# tohuart.net
KiCad netlist of a schematic drawn in EAGLE
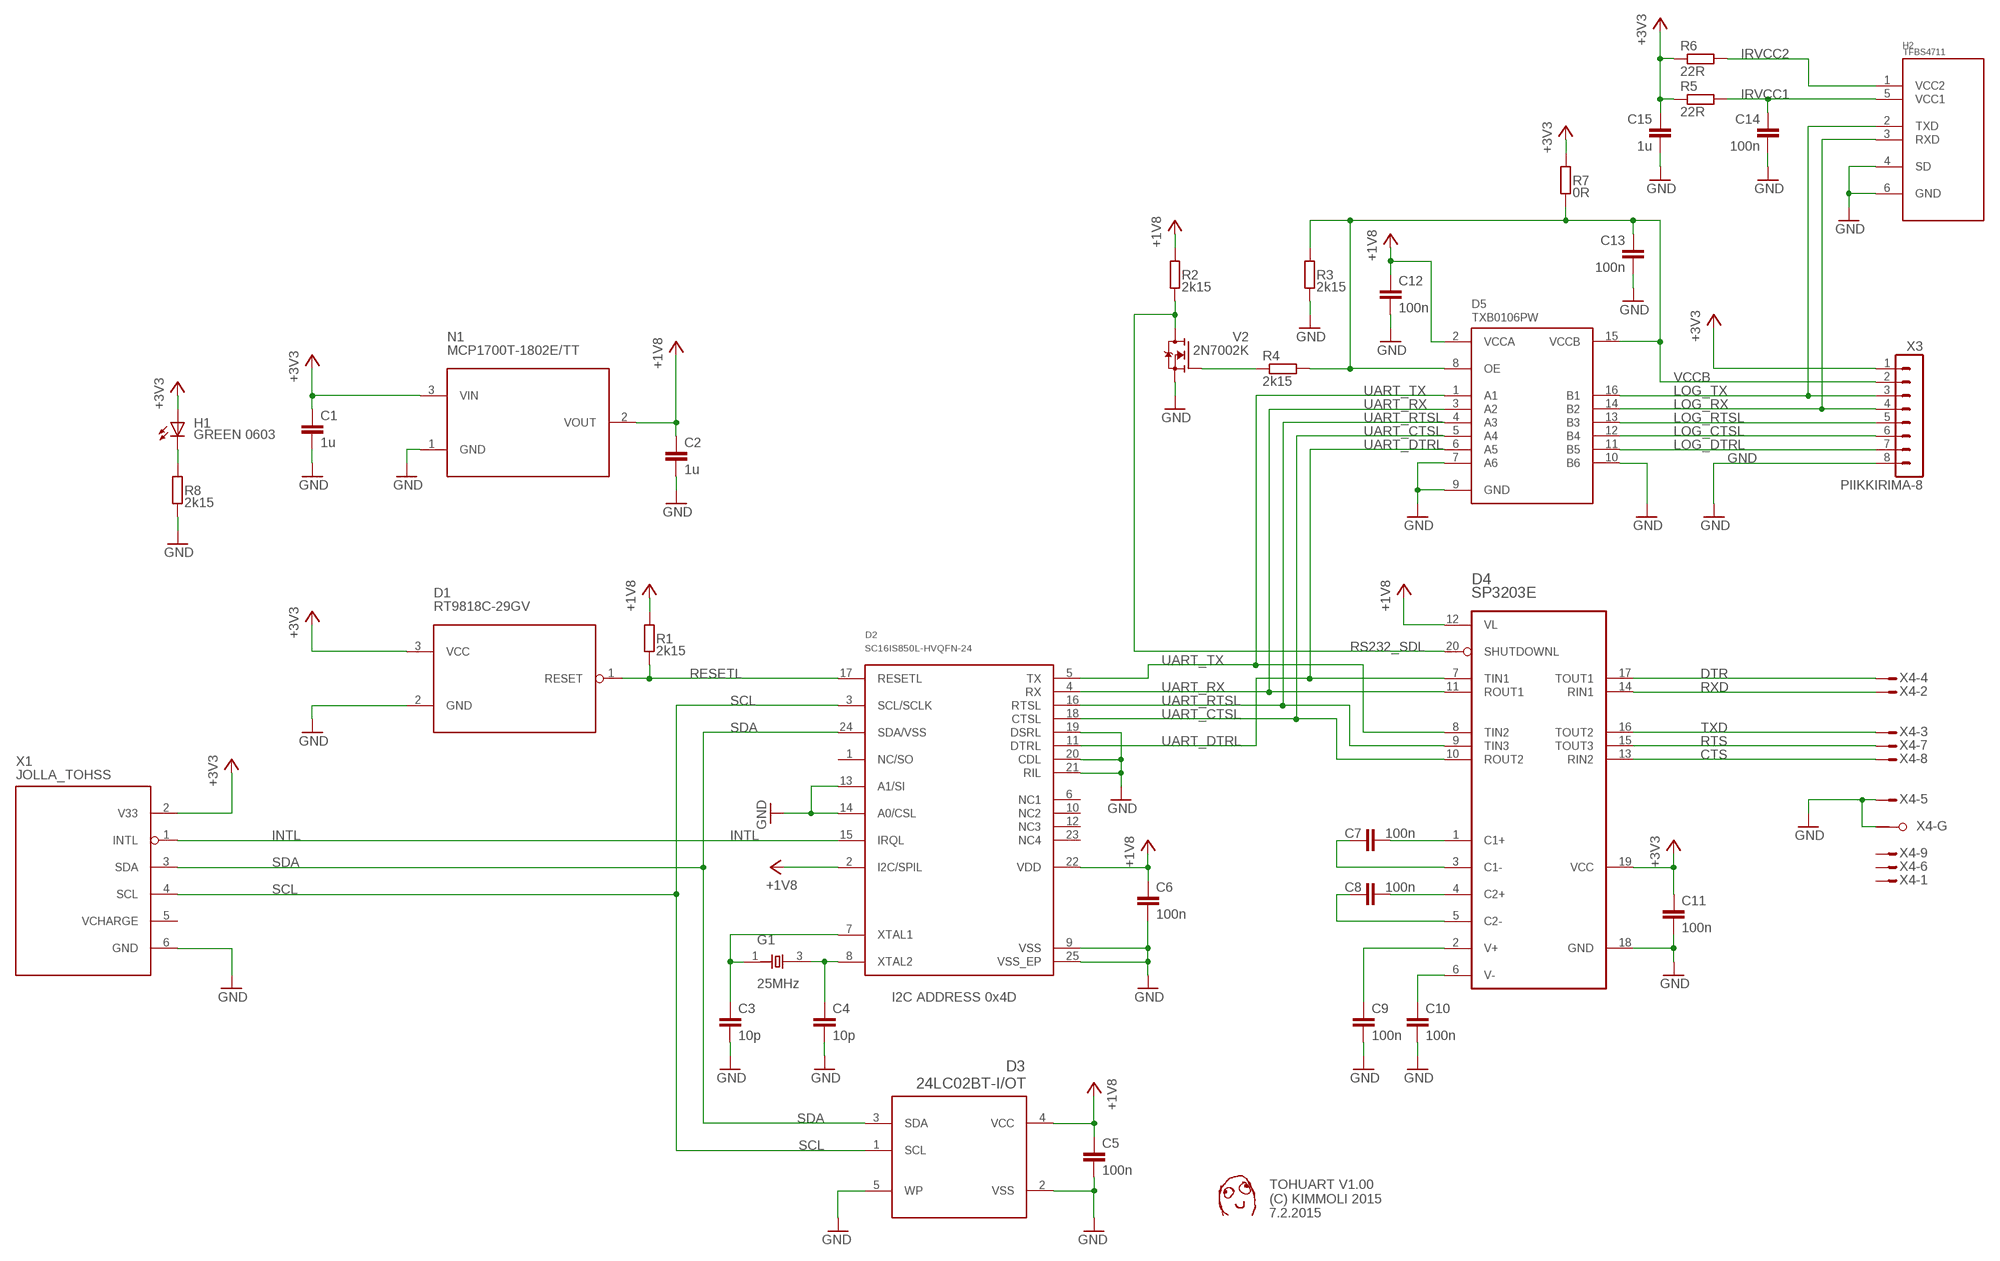
[diagram p0: schematic, sheet 1]

(export (version "E")
  (design (tool "Eeschema 10.0.6"))
  (components
    (comp (ref "C1")
      (value "1u")
      (footprint "eagle-import:C0603")
      (libsource (lib "eagle-import") (part "C-EUC0603"))
    )
    (comp (ref "C2")
      (value "1u")
      (footprint "eagle-import:C0603")
      (libsource (lib "eagle-import") (part "C-EUC0603"))
    )
    (comp (ref "C3")
      (value "10p")
      (footprint "eagle-import:C0603")
      (libsource (lib "eagle-import") (part "C-EUC0603"))
    )
    (comp (ref "C4")
      (value "10p")
      (footprint "eagle-import:C0603")
      (libsource (lib "eagle-import") (part "C-EUC0603"))
    )
    (comp (ref "C5")
      (value "100n")
      (footprint "eagle-import:C0603")
      (libsource (lib "eagle-import") (part "C-EUC0603"))
    )
    (comp (ref "C6")
      (value "100n")
      (footprint "eagle-import:C0603")
      (libsource (lib "eagle-import") (part "C-EUC0603"))
    )
    (comp (ref "C7")
      (value "100n")
      (footprint "eagle-import:C0603")
      (libsource (lib "eagle-import") (part "C-EUC0603"))
    )
    (comp (ref "C8")
      (value "100n")
      (footprint "eagle-import:C0603")
      (libsource (lib "eagle-import") (part "C-EUC0603"))
    )
    (comp (ref "C9")
      (value "100n")
      (footprint "eagle-import:C0603")
      (libsource (lib "eagle-import") (part "C-EUC0603"))
    )
    (comp (ref "C10")
      (value "100n")
      (footprint "eagle-import:C0603")
      (libsource (lib "eagle-import") (part "C-EUC0603"))
    )
    (comp (ref "C11")
      (value "100n")
      (footprint "eagle-import:C0603")
      (libsource (lib "eagle-import") (part "C-EUC0603"))
    )
    (comp (ref "C12")
      (value "100n")
      (footprint "eagle-import:C0603")
      (libsource (lib "eagle-import") (part "C-EUC0603"))
    )
    (comp (ref "C13")
      (value "100n")
      (footprint "eagle-import:C0603")
      (libsource (lib "eagle-import") (part "C-EUC0603"))
    )
    (comp (ref "C14")
      (value "100n")
      (footprint "eagle-import:C0603")
      (libsource (lib "eagle-import") (part "C-EUC0603"))
    )
    (comp (ref "C15")
      (value "1u")
      (footprint "eagle-import:C0603")
      (libsource (lib "eagle-import") (part "C-EUC0603"))
    )
    (comp (ref "D1")
      (value "RT9818C-29GV")
      (footprint "eagle-import:SOT23")
      (libsource (lib "eagle-import") (part "RT9818C-29GV"))
    )
    (comp (ref "D2")
      (value "SC16IS850L-HVQFN-24")
      (footprint "eagle-import:HVQFN-24")
      (libsource (lib "eagle-import") (part "SC16IS850L-HVQFN-24"))
    )
    (comp (ref "D3")
      (value "24LC02BT-I/OT")
      (footprint "eagle-import:SOT95P280X145-5N")
      (libsource (lib "eagle-import") (part "24LC02BT-I/OT"))
    )
    (comp (ref "D4")
      (value "SP3203E")
      (footprint "eagle-import:TSSOP-20")
      (libsource (lib "eagle-import") (part "SP3203E"))
    )
    (comp (ref "D5")
      (value "TXB0106PW")
      (footprint "eagle-import:TSSOP-16-065")
      (libsource (lib "eagle-import") (part "TXB0106PW"))
    )
    (comp (ref "G1")
      (value "25MHz")
      (footprint "eagle-import:X_3225")
      (libsource (lib "eagle-import") (part "XTAL_3225_SMD"))
    )
    (comp (ref "H1")
      (value "GREEN 0603")
      (footprint "eagle-import:CHIP-LED0603")
      (libsource (lib "eagle-import") (part "LEDCHIP-LED0603"))
    )
    (comp (ref "H2")
      (value "TFBS4711")
      (footprint "eagle-import:TFBS4711")
      (libsource (lib "eagle-import") (part "TFBS4711"))
    )
    (comp (ref "N1")
      (value "MCP1700T-1802E/TT")
      (footprint "eagle-import:SOT23")
      (libsource (lib "eagle-import") (part "MCP1700T-1802E/TT"))
    )
    (comp (ref "R1")
      (value "2k15")
      (footprint "eagle-import:R0603")
      (libsource (lib "eagle-import") (part "R-EU_R0603"))
    )
    (comp (ref "R2")
      (value "2k15")
      (footprint "eagle-import:R0603")
      (libsource (lib "eagle-import") (part "R-EU_R0603"))
    )
    (comp (ref "R3")
      (value "2k15")
      (footprint "eagle-import:R0603")
      (libsource (lib "eagle-import") (part "R-EU_R0603"))
    )
    (comp (ref "R4")
      (value "2k15")
      (footprint "eagle-import:R0603")
      (libsource (lib "eagle-import") (part "R-EU_R0603"))
    )
    (comp (ref "R5")
      (value "22R")
      (footprint "eagle-import:R0603")
      (libsource (lib "eagle-import") (part "R-EU_R0603"))
    )
    (comp (ref "R6")
      (value "22R")
      (footprint "eagle-import:R0603")
      (libsource (lib "eagle-import") (part "R-EU_R0603"))
    )
    (comp (ref "R7")
      (value "0R")
      (footprint "eagle-import:R0603")
      (libsource (lib "eagle-import") (part "R-EU_R0603"))
    )
    (comp (ref "R8")
      (value "2k15")
      (footprint "eagle-import:R0603")
      (libsource (lib "eagle-import") (part "R-EU_R0603"))
    )
    (comp (ref "U$1")
      (value "DAFUG")
      (footprint "eagle-import:DAFUG")
      (libsource (lib "eagle-import") (part "DAFUG"))
    )
    (comp (ref "V2")
      (value "2N7002K")
      (footprint "eagle-import:SOT23")
      (libsource (lib "eagle-import") (part "2N7002K"))
    )
    (comp (ref "X1")
      (value "JOLLA_TOHSS")
      (footprint "eagle-import:JOLLA_TOH_POGOPADS")
      (libsource (lib "eagle-import") (part "JOLLA_TOHSS"))
    )
    (comp (ref "X3")
      (value "PIIKKIRIMA-8")
      (footprint "eagle-import:PIIKKIRIMA-8")
      (libsource (lib "eagle-import") (part "PIIKKIRIMA-8"))
    )
    (comp (ref "X4")
      (value "M09VPS")
      (footprint "eagle-import:M09VP")
      (libsource (lib "eagle-import") (part "M09VPS"))
    )
  )
  (nets
    (net (code "1") (name "+1V8") (class "Default")
      (node (ref "C12") (pin "1") (pinfunction "1_1") (pintype "passive"))
      (node (ref "C2") (pin "1") (pinfunction "1_1") (pintype "passive"))
      (node (ref "C5") (pin "1") (pinfunction "1_1") (pintype "passive"))
      (node (ref "C6") (pin "1") (pinfunction "1_1") (pintype "passive"))
      (node (ref "D2") (pin "2") (pinfunction "I2C/SPIL_2") (pintype "bidirectional"))
      (node (ref "D2") (pin "22") (pinfunction "VDD_22") (pintype "bidirectional"))
      (node (ref "D3") (pin "4") (pinfunction "VCC_4") (pintype "power_in"))
      (node (ref "D4") (pin "12") (pinfunction "VL_12") (pintype "passive"))
      (node (ref "D5") (pin "2") (pinfunction "VCCA_2") (pintype "bidirectional"))
      (node (ref "N1") (pin "2") (pinfunction "VOUT_2") (pintype "bidirectional"))
      (node (ref "R1") (pin "2") (pinfunction "2_2") (pintype "passive"))
      (node (ref "R2") (pin "2") (pinfunction "2_2") (pintype "passive"))
    )
    (net (code "2") (name "+3V3") (class "Default")
      (node (ref "C1") (pin "1") (pinfunction "1_1") (pintype "passive"))
      (node (ref "C11") (pin "1") (pinfunction "1_1") (pintype "passive"))
      (node (ref "C15") (pin "1") (pinfunction "1_1") (pintype "passive"))
      (node (ref "D1") (pin "3") (pinfunction "VCC_3") (pintype "bidirectional"))
      (node (ref "D4") (pin "19") (pinfunction "VCC_19") (pintype "power_in"))
      (node (ref "H1") (pin "A") (pinfunction "A_A") (pintype "passive"))
      (node (ref "N1") (pin "3") (pinfunction "VIN_3") (pintype "bidirectional"))
      (node (ref "R5") (pin "1") (pinfunction "1_1") (pintype "passive"))
      (node (ref "R6") (pin "1") (pinfunction "1_1") (pintype "passive"))
      (node (ref "R7") (pin "2") (pinfunction "2_2") (pintype "passive"))
      (node (ref "X1") (pin "2") (pinfunction "V33_2") (pintype "bidirectional"))
      (node (ref "X3") (pin "1") (pinfunction "1_1") (pintype "passive"))
    )
    (net (code "3") (name "/CTS") (class "Default")
      (node (ref "D4") (pin "13") (pinfunction "RIN2_13") (pintype "input"))
      (node (ref "X4") (pin "8") (pinfunction "M_8") (pintype "passive"))
    )
    (net (code "4") (name "/DTR") (class "Default")
      (node (ref "D4") (pin "17") (pinfunction "TOUT1_17") (pintype "output"))
      (node (ref "X4") (pin "4") (pinfunction "M_4") (pintype "passive"))
    )
    (net (code "5") (name "/INTL") (class "Default")
      (node (ref "D2") (pin "15") (pinfunction "IRQL_15") (pintype "bidirectional"))
      (node (ref "X1") (pin "1") (pinfunction "INTL_1") (pintype "bidirectional"))
    )
    (net (code "6") (name "/IRVCC1") (class "Default")
      (node (ref "C14") (pin "1") (pinfunction "1_1") (pintype "passive"))
      (node (ref "H2") (pin "5") (pinfunction "VCC1_5") (pintype "bidirectional"))
      (node (ref "R5") (pin "2") (pinfunction "2_2") (pintype "passive"))
    )
    (net (code "7") (name "/IRVCC2") (class "Default")
      (node (ref "H2") (pin "1") (pinfunction "VCC2_1") (pintype "bidirectional"))
      (node (ref "R6") (pin "2") (pinfunction "2_2") (pintype "passive"))
    )
    (net (code "8") (name "/LOG_CTSL") (class "Default")
      (node (ref "D5") (pin "12") (pinfunction "B4_12") (pintype "bidirectional"))
      (node (ref "X3") (pin "6") (pinfunction "6_6") (pintype "passive"))
    )
    (net (code "9") (name "/LOG_DTRL") (class "Default")
      (node (ref "D5") (pin "11") (pinfunction "B5_11") (pintype "bidirectional"))
      (node (ref "X3") (pin "7") (pinfunction "7_7") (pintype "passive"))
    )
    (net (code "10") (name "/LOG_RTSL") (class "Default")
      (node (ref "D5") (pin "13") (pinfunction "B3_13") (pintype "bidirectional"))
      (node (ref "X3") (pin "5") (pinfunction "5_5") (pintype "passive"))
    )
    (net (code "11") (name "/LOG_RX") (class "Default")
      (node (ref "D5") (pin "14") (pinfunction "B2_14") (pintype "bidirectional"))
      (node (ref "H2") (pin "3") (pinfunction "RXD_3") (pintype "bidirectional"))
      (node (ref "X3") (pin "4") (pinfunction "4_4") (pintype "passive"))
    )
    (net (code "12") (name "/LOG_TX") (class "Default")
      (node (ref "D5") (pin "16") (pinfunction "B1_16") (pintype "bidirectional"))
      (node (ref "H2") (pin "2") (pinfunction "TXD_2") (pintype "bidirectional"))
      (node (ref "X3") (pin "3") (pinfunction "3_3") (pintype "passive"))
    )
    (net (code "13") (name "/RESETL") (class "Default")
      (node (ref "D1") (pin "1") (pinfunction "RESET_1") (pintype "bidirectional"))
      (node (ref "D2") (pin "17") (pinfunction "RESETL_17") (pintype "bidirectional"))
      (node (ref "R1") (pin "1") (pinfunction "1_1") (pintype "passive"))
    )
    (net (code "14") (name "/RS232_SDL") (class "Default")
      (node (ref "D4") (pin "20") (pinfunction "SHUTDOWNL_20") (pintype "bidirectional"))
      (node (ref "R2") (pin "1") (pinfunction "1_1") (pintype "passive"))
      (node (ref "V2") (pin "3") (pinfunction "D_3") (pintype "passive"))
    )
    (net (code "15") (name "/RTS") (class "Default")
      (node (ref "D4") (pin "15") (pinfunction "TOUT3_15") (pintype "output"))
      (node (ref "X4") (pin "7") (pinfunction "M_7") (pintype "passive"))
    )
    (net (code "16") (name "/RXD") (class "Default")
      (node (ref "D4") (pin "14") (pinfunction "RIN1_14") (pintype "input"))
      (node (ref "X4") (pin "2") (pinfunction "M_2") (pintype "passive"))
    )
    (net (code "17") (name "/SCL") (class "Default")
      (node (ref "D2") (pin "3") (pinfunction "SCL/SCLK_3") (pintype "bidirectional"))
      (node (ref "D3") (pin "1") (pinfunction "SCL_1") (pintype "input"))
      (node (ref "X1") (pin "4") (pinfunction "SCL_4") (pintype "bidirectional"))
    )
    (net (code "18") (name "/SDA") (class "Default")
      (node (ref "D2") (pin "24") (pinfunction "SDA/VSS_24") (pintype "bidirectional"))
      (node (ref "D3") (pin "3") (pinfunction "SDA_3") (pintype "bidirectional"))
      (node (ref "X1") (pin "3") (pinfunction "SDA_3") (pintype "bidirectional"))
    )
    (net (code "19") (name "/TXD") (class "Default")
      (node (ref "D4") (pin "16") (pinfunction "TOUT2_16") (pintype "output"))
      (node (ref "X4") (pin "3") (pinfunction "M_3") (pintype "passive"))
    )
    (net (code "20") (name "/UART_CTSL") (class "Default")
      (node (ref "D2") (pin "18") (pinfunction "CTSL_18") (pintype "bidirectional"))
      (node (ref "D4") (pin "10") (pinfunction "ROUT2_10") (pintype "output"))
      (node (ref "D5") (pin "5") (pinfunction "A4_5") (pintype "bidirectional"))
    )
    (net (code "21") (name "/UART_DTRL") (class "Default")
      (node (ref "D2") (pin "11") (pinfunction "DTRL_11") (pintype "bidirectional"))
      (node (ref "D4") (pin "7") (pinfunction "TIN1_7") (pintype "input"))
      (node (ref "D5") (pin "6") (pinfunction "A5_6") (pintype "bidirectional"))
    )
    (net (code "22") (name "/UART_RTSL") (class "Default")
      (node (ref "D2") (pin "16") (pinfunction "RTSL_16") (pintype "bidirectional"))
      (node (ref "D4") (pin "9") (pinfunction "TIN3_9") (pintype "input"))
      (node (ref "D5") (pin "4") (pinfunction "A3_4") (pintype "bidirectional"))
    )
    (net (code "23") (name "/UART_RX") (class "Default")
      (node (ref "D2") (pin "4") (pinfunction "RX_4") (pintype "bidirectional"))
      (node (ref "D4") (pin "11") (pinfunction "ROUT1_11") (pintype "output"))
      (node (ref "D5") (pin "3") (pinfunction "A2_3") (pintype "bidirectional"))
    )
    (net (code "24") (name "/UART_TX") (class "Default")
      (node (ref "D2") (pin "5") (pinfunction "TX_5") (pintype "bidirectional"))
      (node (ref "D4") (pin "8") (pinfunction "TIN2_8") (pintype "input"))
      (node (ref "D5") (pin "1") (pinfunction "A1_1") (pintype "bidirectional"))
    )
    (net (code "25") (name "/VCCB") (class "Default")
      (node (ref "C13") (pin "1") (pinfunction "1_1") (pintype "passive"))
      (node (ref "D5") (pin "15") (pinfunction "VCCB_15") (pintype "bidirectional"))
      (node (ref "D5") (pin "8") (pinfunction "OE_8") (pintype "bidirectional"))
      (node (ref "R3") (pin "2") (pinfunction "2_2") (pintype "passive"))
      (node (ref "R4") (pin "2") (pinfunction "2_2") (pintype "passive"))
      (node (ref "R7") (pin "1") (pinfunction "1_1") (pintype "passive"))
      (node (ref "X3") (pin "2") (pinfunction "2_2") (pintype "passive"))
    )
    (net (code "26") (name "GND") (class "Default")
      (node (ref "C1") (pin "2") (pinfunction "2_2") (pintype "passive"))
      (node (ref "C10") (pin "2") (pinfunction "2_2") (pintype "passive"))
      (node (ref "C11") (pin "2") (pinfunction "2_2") (pintype "passive"))
      (node (ref "C12") (pin "2") (pinfunction "2_2") (pintype "passive"))
      (node (ref "C13") (pin "2") (pinfunction "2_2") (pintype "passive"))
      (node (ref "C14") (pin "2") (pinfunction "2_2") (pintype "passive"))
      (node (ref "C15") (pin "2") (pinfunction "2_2") (pintype "passive"))
      (node (ref "C2") (pin "2") (pinfunction "2_2") (pintype "passive"))
      (node (ref "C3") (pin "2") (pinfunction "2_2") (pintype "passive"))
      (node (ref "C4") (pin "2") (pinfunction "2_2") (pintype "passive"))
      (node (ref "C5") (pin "2") (pinfunction "2_2") (pintype "passive"))
      (node (ref "C6") (pin "2") (pinfunction "2_2") (pintype "passive"))
      (node (ref "C9") (pin "2") (pinfunction "2_2") (pintype "passive"))
      (node (ref "D1") (pin "2") (pinfunction "GND_2") (pintype "bidirectional"))
      (node (ref "D2") (pin "13") (pinfunction "A1/SI_13") (pintype "bidirectional"))
      (node (ref "D2") (pin "14") (pinfunction "A0/CSL_14") (pintype "bidirectional"))
      (node (ref "D2") (pin "19") (pinfunction "DSRL_19") (pintype "bidirectional"))
      (node (ref "D2") (pin "20") (pinfunction "CDL_20") (pintype "bidirectional"))
      (node (ref "D2") (pin "21") (pinfunction "RIL_21") (pintype "bidirectional"))
      (node (ref "D2") (pin "25") (pinfunction "VSS_EP_25") (pintype "bidirectional"))
      (node (ref "D2") (pin "9") (pinfunction "VSS_9") (pintype "bidirectional"))
      (node (ref "D3") (pin "2") (pinfunction "VSS_2") (pintype "passive"))
      (node (ref "D3") (pin "5") (pinfunction "WP_5") (pintype "input"))
      (node (ref "D4") (pin "18") (pinfunction "GND_18") (pintype "passive"))
      (node (ref "D5") (pin "10") (pinfunction "B6_10") (pintype "bidirectional"))
      (node (ref "D5") (pin "7") (pinfunction "A6_7") (pintype "bidirectional"))
      (node (ref "D5") (pin "9") (pinfunction "GND_9") (pintype "bidirectional"))
      (node (ref "H2") (pin "4") (pinfunction "SD_4") (pintype "bidirectional"))
      (node (ref "H2") (pin "6") (pinfunction "GND_6") (pintype "bidirectional"))
      (node (ref "N1") (pin "1") (pinfunction "GND_1") (pintype "bidirectional"))
      (node (ref "R3") (pin "1") (pinfunction "1_1") (pintype "passive"))
      (node (ref "R8") (pin "1") (pinfunction "1_1") (pintype "passive"))
      (node (ref "V2") (pin "2") (pinfunction "S_2") (pintype "passive"))
      (node (ref "X1") (pin "6") (pinfunction "GND_6") (pintype "bidirectional"))
      (node (ref "X3") (pin "8") (pinfunction "8_8") (pintype "passive"))
      (node (ref "X4") (pin "5") (pinfunction "M_5") (pintype "passive"))
      (node (ref "X4") (pin "G1") (pinfunction "G1_G1") (pintype "passive"))
    )
    (net (code "27") (name "Net-(D2-XTAL1)") (class "Default")
      (node (ref "C3") (pin "1") (pinfunction "1_1") (pintype "passive"))
      (node (ref "D2") (pin "7") (pinfunction "XTAL1_7") (pintype "bidirectional"))
      (node (ref "G1") (pin "1") (pinfunction "X1_1") (pintype "bidirectional"))
    )
    (net (code "28") (name "Net-(D2-XTAL2)") (class "Default")
      (node (ref "C4") (pin "1") (pinfunction "1_1") (pintype "passive"))
      (node (ref "D2") (pin "8") (pinfunction "XTAL2_8") (pintype "bidirectional"))
      (node (ref "G1") (pin "3") (pinfunction "X2_3") (pintype "bidirectional"))
    )
    (net (code "29") (name "Net-(D4-C1+)") (class "Default")
      (node (ref "C7") (pin "2") (pinfunction "2_2") (pintype "passive"))
      (node (ref "D4") (pin "1") (pinfunction "C1+_1") (pintype "passive"))
    )
    (net (code "30") (name "Net-(D4-C1-)") (class "Default")
      (node (ref "C7") (pin "1") (pinfunction "1_1") (pintype "passive"))
      (node (ref "D4") (pin "3") (pinfunction "C1-_3") (pintype "passive"))
    )
    (net (code "31") (name "Net-(D4-C2+)") (class "Default")
      (node (ref "C8") (pin "2") (pinfunction "2_2") (pintype "passive"))
      (node (ref "D4") (pin "4") (pinfunction "C2+_4") (pintype "passive"))
    )
    (net (code "32") (name "Net-(D4-C2-)") (class "Default")
      (node (ref "C8") (pin "1") (pinfunction "1_1") (pintype "passive"))
      (node (ref "D4") (pin "5") (pinfunction "C2-_5") (pintype "passive"))
    )
    (net (code "33") (name "Net-(D4-V+)") (class "Default")
      (node (ref "C9") (pin "1") (pinfunction "1_1") (pintype "passive"))
      (node (ref "D4") (pin "2") (pinfunction "V+_2") (pintype "power_in"))
    )
    (net (code "34") (name "Net-(D4-V-)") (class "Default")
      (node (ref "C10") (pin "1") (pinfunction "1_1") (pintype "passive"))
      (node (ref "D4") (pin "6") (pinfunction "V-_6") (pintype "power_in"))
    )
    (net (code "35") (name "Net-(H1-PadC)") (class "Default")
      (node (ref "H1") (pin "C") (pinfunction "C_C") (pintype "passive"))
      (node (ref "R8") (pin "2") (pinfunction "2_2") (pintype "passive"))
    )
    (net (code "36") (name "Net-(V2-G)") (class "Default")
      (node (ref "R4") (pin "1") (pinfunction "1_1") (pintype "passive"))
      (node (ref "V2") (pin "1") (pinfunction "G_1") (pintype "passive"))
    )
    (net (code "37") (name "unconnected-(D2-NC1-Pad6)") (class "Default")
      (node (ref "D2") (pin "6") (pinfunction "NC1_6") (pintype "bidirectional"))
    )
    (net (code "38") (name "unconnected-(D2-NC2-Pad10)") (class "Default")
      (node (ref "D2") (pin "10") (pinfunction "NC2_10") (pintype "bidirectional"))
    )
    (net (code "39") (name "unconnected-(D2-NC3-Pad12)") (class "Default")
      (node (ref "D2") (pin "12") (pinfunction "NC3_12") (pintype "bidirectional"))
    )
    (net (code "40") (name "unconnected-(D2-NC4-Pad23)") (class "Default")
      (node (ref "D2") (pin "23") (pinfunction "NC4_23") (pintype "bidirectional"))
    )
    (net (code "41") (name "unconnected-(D2-NC{slash}SO-Pad1)") (class "Default")
      (node (ref "D2") (pin "1") (pinfunction "NC/SO_1") (pintype "bidirectional"))
    )
    (net (code "42") (name "unconnected-(X1-VCHARGE-Pad5)") (class "Default")
      (node (ref "X1") (pin "5") (pinfunction "VCHARGE_5") (pintype "bidirectional"))
    )
    (net (code "43") (name "unconnected-(X4-PadG2)") (class "Default")
      (node (ref "X4") (pin "G2") (pinfunction "G2_G2") (pintype "passive"))
    )
    (net (code "44") (name "unconnected-(X4A-M-Pad1)") (class "Default")
      (node (ref "X4") (pin "1") (pinfunction "M_1") (pintype "passive"))
    )
    (net (code "45") (name "unconnected-(X4F-M-Pad6)") (class "Default")
      (node (ref "X4") (pin "6") (pinfunction "M_6") (pintype "passive"))
    )
    (net (code "46") (name "unconnected-(X4I-M-Pad9)") (class "Default")
      (node (ref "X4") (pin "9") (pinfunction "M_9") (pintype "passive"))
    )
  )
)
